# LVGBufAmp.net
KiCad netlist of a schematic drawn in Altium Designer
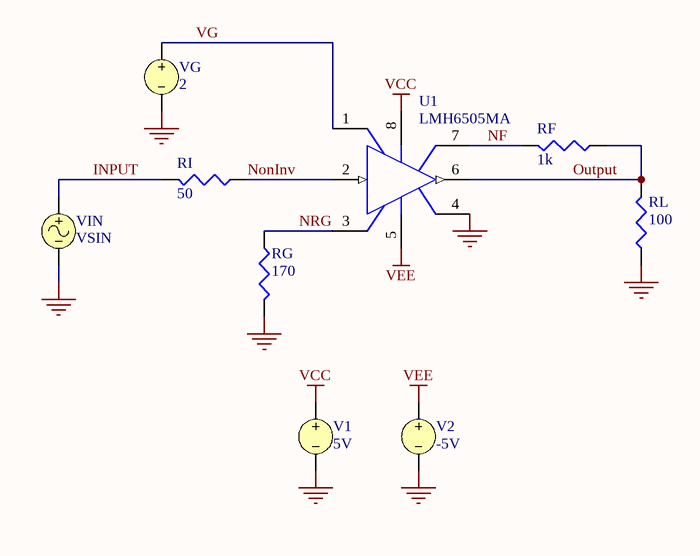
[diagram p0: LVGBufAmp.schdoc]

(export (version "E")
  (design (tool "Eeschema 10.0.6"))
  (components
    (comp (ref "RF")
      (value "1k")
      (description "Resistor")
      (fields (field (name "Comment") "100k"))
      (libsource (lib "*") (part "RES"))
    )
    (comp (ref "RG")
      (value "170")
      (description "Resistor")
      (fields (field (name "Comment") "10k"))
      (libsource (lib "") (part "RES_2"))
    )
    (comp (ref "RI")
      (value "50")
      (description "Resistor")
      (fields (field (name "Comment") "10k"))
      (libsource (lib "*") (part "RES"))
    )
    (comp (ref "RL")
      (value "100")
      (description "Resistor")
      (fields (field (name "Comment") "25k"))
      (libsource (lib "") (part "RES_1"))
    )
    (comp (ref "U1")
      (value "LMH6505MA")
      (footprint "M08A_N")
      (description "Wideband, Low Power, Linear-in-dB, Variable Gain Amplifier")
      (fields
        (field (name "MANUFACTURER") "National Semiconductor")
        (field (name "DIGIKEYPARTNUMBER") "LMH6505MA-ND")
        (field (name "PUBLISHER") "Altium Limited")
      )
      (libsource (lib "NSC Amplifier with SIM models") (part "LMH6505MA"))
    )
    (comp (ref "V1")
      (value "5V")
      (description "Voltage Source")
      (fields (field (name "Comment") "12V"))
      (libsource (lib "*") (part "VSRC"))
    )
    (comp (ref "V2")
      (value "-5V")
      (description "Voltage Source")
      (fields (field (name "Comment") "-12V"))
      (libsource (lib "*") (part "VSRC"))
    )
    (comp (ref "VG")
      (value "2")
      (description "Voltage Source")
      (fields (field (name "Comment") "12V"))
      (libsource (lib "*") (part "VSRC"))
    )
    (comp (ref "VIN")
      (value "VSIN")
      (description "Sinusoidal Voltage Source")
      (libsource (lib "*") (part "VSIN"))
    )
  )
  (nets
    (net (code "1") (name "/INPUT") (class "Default")
      (node (ref "RI") (pin "1") (pinfunction "TOP_1") (pintype "passive"))
      (node (ref "VIN") (pin "1") (pinfunction "1_1") (pintype "passive"))
    )
    (net (code "2") (name "/NF") (class "Default")
      (node (ref "RF") (pin "1") (pinfunction "TOP_1") (pintype "passive"))
      (node (ref "U1") (pin "7") (pinfunction "I-_7") (pintype "passive"))
    )
    (net (code "3") (name "/NRG") (class "Default")
      (node (ref "RG") (pin "2") (pinfunction "BOT_2") (pintype "passive"))
      (node (ref "U1") (pin "3") (pinfunction "RG_3") (pintype "passive"))
    )
    (net (code "4") (name "/NonInv") (class "Default")
      (node (ref "RI") (pin "2") (pinfunction "BOT_2") (pintype "passive"))
      (node (ref "U1") (pin "2") (pinfunction "VIN_2") (pintype "input"))
    )
    (net (code "5") (name "/Output") (class "Default")
      (node (ref "RF") (pin "2") (pinfunction "BOT_2") (pintype "passive"))
      (node (ref "RL") (pin "1") (pinfunction "TOP_1") (pintype "passive"))
      (node (ref "U1") (pin "6") (pinfunction "VOUT_6") (pintype "output"))
    )
    (net (code "6") (name "/VG") (class "Default")
      (node (ref "U1") (pin "1") (pinfunction "VG_1") (pintype "passive"))
      (node (ref "VG") (pin "1") (pinfunction "1_1") (pintype "passive"))
    )
    (net (code "7") (name "GND") (class "Default")
      (node (ref "RG") (pin "1") (pinfunction "TOP_1") (pintype "passive"))
      (node (ref "RL") (pin "2") (pinfunction "BOT_2") (pintype "passive"))
      (node (ref "U1") (pin "4") (pinfunction "GND_4") (pintype "power_in"))
      (node (ref "V1") (pin "2") (pinfunction "2_2") (pintype "passive"))
      (node (ref "V2") (pin "2") (pinfunction "2_2") (pintype "passive"))
      (node (ref "VG") (pin "2") (pinfunction "2_2") (pintype "passive"))
      (node (ref "VIN") (pin "2") (pinfunction "2_2") (pintype "passive"))
    )
    (net (code "8") (name "VCC") (class "Default")
      (node (ref "U1") (pin "8") (pinfunction "V+_8") (pintype "power_in"))
      (node (ref "V1") (pin "1") (pinfunction "1_1") (pintype "passive"))
    )
    (net (code "9") (name "VEE") (class "Default")
      (node (ref "U1") (pin "5") (pinfunction "V-_5") (pintype "power_in"))
      (node (ref "V2") (pin "1") (pinfunction "1_1") (pintype "passive"))
    )
  )
)
